# Receiver_Schematic.net
KiCad netlist of a schematic drawn in Altium Designer
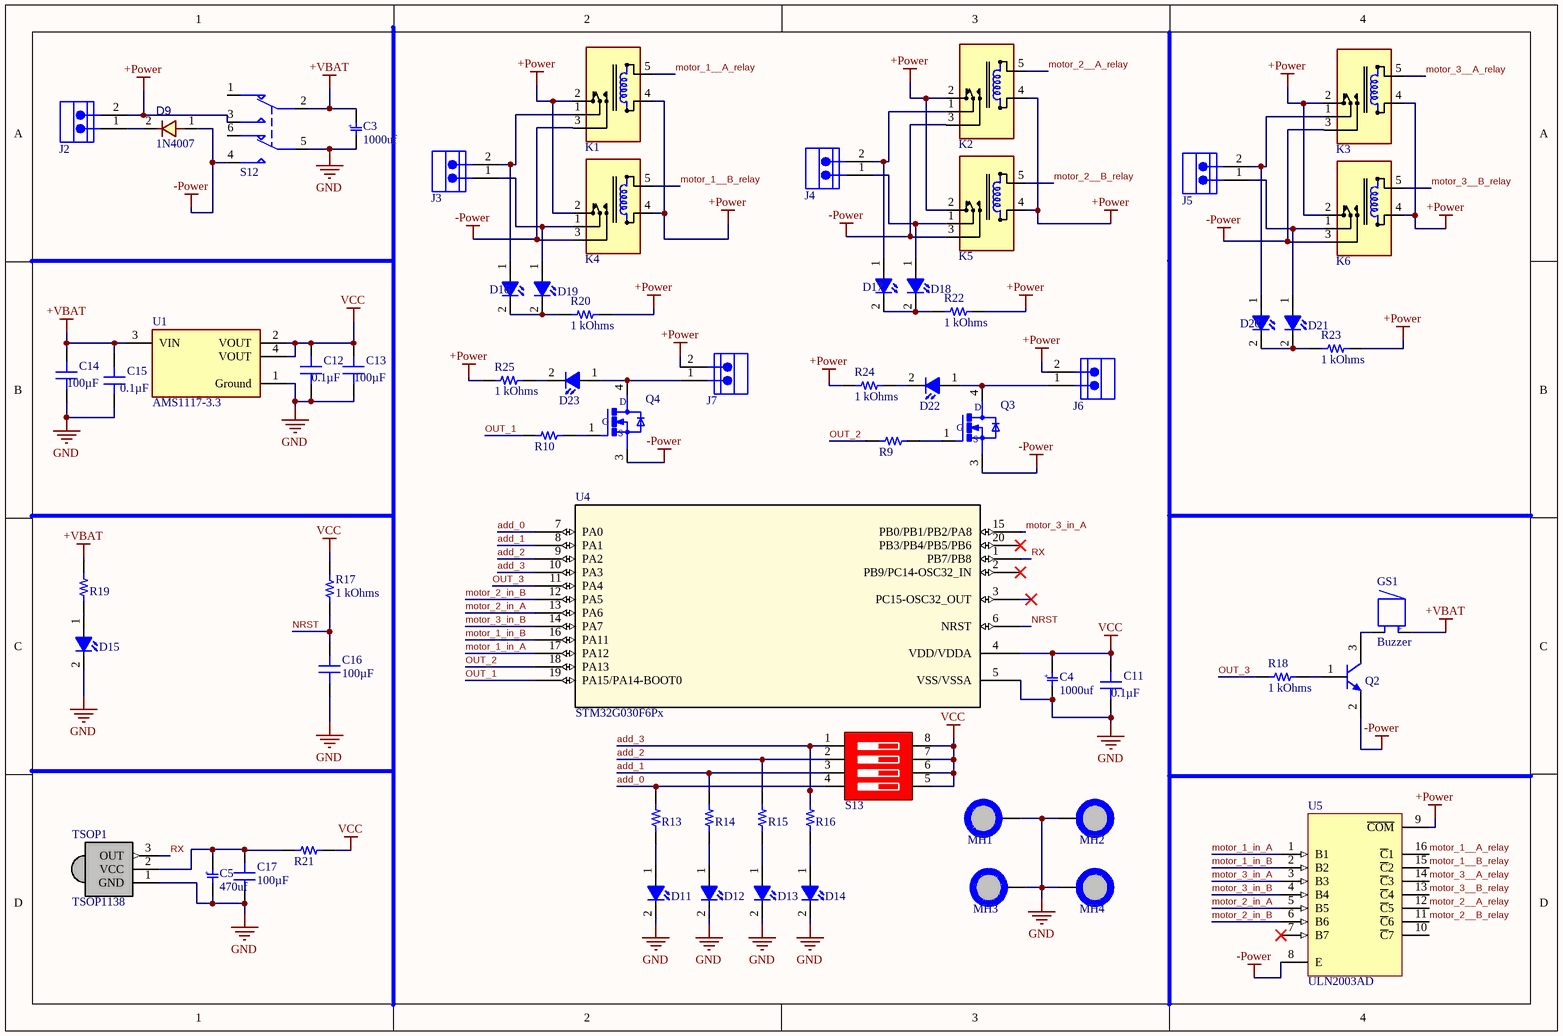
[diagram p0: Receiver_Schematic.SchDoc]

(export (version "E")
  (design (tool "Eeschema 10.0.6"))
  (components
    (comp (ref "C3")
      (value "1000uf")
      (footprint "Cap_3_(3.5mm)")
      (description "Capacitor Electrical THD")
      (libsource (lib "Schlib1") (part "Capacitor Electrical THD"))
    )
    (comp (ref "C4")
      (value "1000uf")
      (footprint "Cap_3_(3.5mm)")
      (description "Capacitor Electrical THD")
      (libsource (lib "Schlib1") (part "Capacitor Electrical THD"))
    )
    (comp (ref "C5")
      (value "470uf")
      (footprint "Cap_3_(3.5mm)")
      (description "Capacitor Electrical THD")
      (libsource (lib "Schlib1") (part "Capacitor Electrical THD"))
    )
    (comp (ref "C11")
      (value "0.1µF")
      (footprint "CAP 0805_2012")
      (description "CAP CER 0805 10% X8R 50V 100NF")
      (fields (field (name "PART NUMBER") "AC0805KKX8R9BB104") (field (name "MANUFACTURER") "Yageo"))
      (libsource (lib "Database_Libs1") (part "Capacitor"))
    )
    (comp (ref "C12")
      (value "0.1µF")
      (footprint "CAP 0805_2012")
      (description "CAP CER 0805 10% X8R 50V 100NF")
      (fields (field (name "PART NUMBER") "AC0805KKX8R9BB104") (field (name "MANUFACTURER") "Yageo"))
      (libsource (lib "Database_Libs1") (part "Capacitor"))
    )
    (comp (ref "C13")
      (value "100µF")
      (footprint "CAP 0805_2012")
      (description "CAP CER 100UF 6.3V X5R 0805")
      (fields
        (field (name "PART NUMBER") "GRM21BR60J107ME15L")
        (field (name "MANUFACTURER") "Murata Electronics")
      )
      (libsource (lib "Database_Libs1") (part "Capacitor"))
    )
    (comp (ref "C14")
      (value "100µF")
      (footprint "CAP 0805_2012")
      (description "CAP CER 100UF 6.3V X5R 0805")
      (fields
        (field (name "PART NUMBER") "GRM21BR60J107ME15L")
        (field (name "MANUFACTURER") "Murata Electronics")
      )
      (libsource (lib "Database_Libs1") (part "Capacitor"))
    )
    (comp (ref "C15")
      (value "0.1µF")
      (footprint "CAP 0805_2012")
      (description "CAP CER 0805 10% X8R 50V 100NF")
      (fields (field (name "PART NUMBER") "AC0805KKX8R9BB104") (field (name "MANUFACTURER") "Yageo"))
      (libsource (lib "Database_Libs1") (part "Capacitor"))
    )
    (comp (ref "C16")
      (value "100µF")
      (footprint "CAP 0805_2012")
      (description "CAP CER 100UF 6.3V X5R 0805")
      (fields
        (field (name "PART NUMBER") "GRM21BR60J107ME15L")
        (field (name "MANUFACTURER") "Murata Electronics")
      )
      (libsource (lib "Database_Libs1") (part "Capacitor"))
    )
    (comp (ref "C17")
      (value "100µF")
      (footprint "CAP 0805_2012")
      (description "CAP CER 100UF 6.3V X5R 0805")
      (fields
        (field (name "PART NUMBER") "GRM21BR60J107ME15L")
        (field (name "MANUFACTURER") "Murata Electronics")
      )
      (libsource (lib "Database_Libs1") (part "Capacitor"))
    )
    (comp (ref "D9")
      (value "1N4007")
      (footprint "D_SMA")
      (description "DIODE, GENERAL PURPOSE, 1000V/1A")
      (fields (field (name "Comment") "1N4007 SMD M7"))
      (libsource (lib "Schlib1") (part "1N4007 SMD M7"))
    )
    (comp (ref "D11")
      (value "LED THD 3mm")
      (footprint "LED THD 3mm (White)")
      (libsource (lib "Schlib1") (part "LED THD 3mm"))
    )
    (comp (ref "D12")
      (value "LED THD 3mm")
      (footprint "LED THD 3mm (White)")
      (libsource (lib "Schlib1") (part "LED THD 3mm"))
    )
    (comp (ref "D13")
      (value "LED THD 3mm")
      (footprint "LED THD 3mm (White)")
      (libsource (lib "Schlib1") (part "LED THD 3mm"))
    )
    (comp (ref "D14")
      (value "LED THD 3mm")
      (footprint "LED THD 3mm (White)")
      (libsource (lib "Schlib1") (part "LED THD 3mm"))
    )
    (comp (ref "D15")
      (value "LED THD 3mm")
      (footprint "LED THD 3mm (White)")
      (libsource (lib "Schlib1") (part "LED THD 3mm"))
    )
    (comp (ref "D16")
      (value "LED THD 3mm")
      (footprint "LED THD 3mm (White)")
      (libsource (lib "Schlib1") (part "LED THD 3mm"))
    )
    (comp (ref "D17")
      (value "LED THD 3mm")
      (footprint "LED THD 3mm (White)")
      (libsource (lib "Schlib1") (part "LED THD 3mm"))
    )
    (comp (ref "D18")
      (value "LED THD 3mm")
      (footprint "LED THD 3mm (White)")
      (libsource (lib "Schlib1") (part "LED THD 3mm"))
    )
    (comp (ref "D19")
      (value "LED THD 3mm")
      (footprint "LED THD 3mm (White)")
      (libsource (lib "Schlib1") (part "LED THD 3mm"))
    )
    (comp (ref "D20")
      (value "LED THD 3mm")
      (footprint "LED THD 3mm (White)")
      (libsource (lib "Schlib1") (part "LED THD 3mm"))
    )
    (comp (ref "D21")
      (value "LED THD 3mm")
      (footprint "LED THD 3mm (White)")
      (libsource (lib "Schlib1") (part "LED THD 3mm"))
    )
    (comp (ref "D22")
      (value "LED THD 3mm")
      (footprint "LED THD 3mm (White)")
      (libsource (lib "Schlib1") (part "LED THD 3mm"))
    )
    (comp (ref "D23")
      (value "LED THD 3mm")
      (footprint "LED THD 3mm (White)")
      (libsource (lib "Schlib1") (part "LED THD 3mm"))
    )
    (comp (ref "GS1")
      (value "Buzzer")
      (footprint "BZ_SJ")
      (description "Magnetic Transducer Buzzer")
      (fields (field (name "DESIGNER") "Eng. Saeid Jorablo") (field (name "PUBLISHER") "SJ Unlimited"))
      (libsource (lib "Schlib1") (part "Buzzer"))
    )
    (comp (ref "J2")
      (value "Socket Blue 2")
      (footprint "Socket Blue 2")
      (libsource (lib "Schlib1") (part "Socket Blue 2"))
    )
    (comp (ref "J3")
      (value "Socket Blue 2")
      (footprint "Socket Blue 2")
      (libsource (lib "Schlib1") (part "Socket Blue 2"))
    )
    (comp (ref "J4")
      (value "Socket Blue 2")
      (footprint "Socket Blue 2")
      (libsource (lib "Schlib1") (part "Socket Blue 2"))
    )
    (comp (ref "J5")
      (value "Socket Blue 2")
      (footprint "Socket Blue 2")
      (libsource (lib "Schlib1") (part "Socket Blue 2"))
    )
    (comp (ref "J6")
      (value "Socket Blue 2")
      (footprint "Socket Blue 2")
      (libsource (lib "Schlib1") (part "Socket Blue 2"))
    )
    (comp (ref "J7")
      (value "Socket Blue 2")
      (footprint "Socket Blue 2")
      (libsource (lib "Schlib1") (part "Socket Blue 2"))
    )
    (comp (ref "K1")
      (value "RELAY SPST 5 Pin Millon")
      (footprint "REL_SPDT_5_2216")
      (description "Relay")
      (libsource (lib "Schlib1") (part "RELAY SPST 5 Pin Millon"))
    )
    (comp (ref "K2")
      (value "RELAY SPST 5 Pin Millon")
      (footprint "REL_SPDT_5_2216")
      (description "Relay")
      (libsource (lib "Schlib1") (part "RELAY SPST 5 Pin Millon"))
    )
    (comp (ref "K3")
      (value "RELAY SPST 5 Pin Millon")
      (footprint "REL_SPDT_5_2216")
      (description "Relay")
      (libsource (lib "Schlib1") (part "RELAY SPST 5 Pin Millon"))
    )
    (comp (ref "K4")
      (value "RELAY SPST 5 Pin Millon")
      (footprint "REL_SPDT_5_2216")
      (description "Relay")
      (libsource (lib "Schlib1") (part "RELAY SPST 5 Pin Millon"))
    )
    (comp (ref "K5")
      (value "RELAY SPST 5 Pin Millon")
      (footprint "REL_SPDT_5_2216")
      (description "Relay")
      (libsource (lib "Schlib1") (part "RELAY SPST 5 Pin Millon"))
    )
    (comp (ref "K6")
      (value "RELAY SPST 5 Pin Millon")
      (footprint "REL_SPDT_5_2216")
      (description "Relay")
      (libsource (lib "Schlib1") (part "RELAY SPST 5 Pin Millon"))
    )
    (comp (ref "MH1")
      (value "MH_7.4mmC_3.2mmD")
      (footprint "MH_7.4mmC_3.2mmD")
      (description "MH_7.4MM Diameter,3.2mm Drill")
      (libsource (lib "Schlib1") (part "MH_7.4mmC_3.2mmD"))
    )
    (comp (ref "MH2")
      (value "MH_7.4mmC_3.2mmD")
      (footprint "MH_7.4mmC_3.2mmD")
      (description "MH_7.4MM Diameter,3.2mm Drill")
      (libsource (lib "Schlib1") (part "MH_7.4mmC_3.2mmD"))
    )
    (comp (ref "MH3")
      (value "MH_7.4mmC_3.2mmD")
      (footprint "MH_7.4mmC_3.2mmD")
      (description "MH_7.4MM Diameter,3.2mm Drill")
      (libsource (lib "Schlib1") (part "MH_7.4mmC_3.2mmD"))
    )
    (comp (ref "MH4")
      (value "MH_7.4mmC_3.2mmD")
      (footprint "MH_7.4mmC_3.2mmD")
      (description "MH_7.4MM Diameter,3.2mm Drill")
      (libsource (lib "Schlib1") (part "MH_7.4mmC_3.2mmD"))
    )
    (comp (ref "Q2")
      (value "MMBT2222A-7-F")
      (footprint "DIODES SOT-23-3")
      (description "TRANS NPN 40V 0.6A SMD SOT23-3")
      (fields (field (name "MANUFACTURER") "Diodes Incorporated"))
      (libsource (lib "Database_Libs1") (part "DIODES INC NPN SOT-23-3"))
    )
    (comp (ref "Q3")
      (value "PHD45N03LTA")
      (footprint "PcbLib1:TO228P1000X238-3N")
      (description "Bipolar Transistors - BJT")
      (fields (field (name "MF") "NXP USA"))
      (libsource (lib "Schlib1") (part "PHD45N03LTA"))
    )
    (comp (ref "Q4")
      (value "PHD45N03LTA")
      (footprint "PcbLib1:TO228P1000X238-3N")
      (description "Bipolar Transistors - BJT")
      (fields (field (name "MF") "NXP USA"))
      (libsource (lib "Schlib1") (part "PHD45N03LTA"))
    )
    (comp (ref "R9")
      (value "100 Ohms")
      (footprint "RES 0805_2012")
      (description "RES SMD 100 OHM 1% 0.4W 0805")
      (fields (field (name "PART NUMBER") "RCS0805100RFKEA") (field (name "MANUFACTURER") "Vishay Dale"))
      (libsource (lib "Database_Libs1") (part "Resistor"))
    )
    (comp (ref "R10")
      (value "100 Ohms")
      (footprint "RES 0805_2012")
      (description "RES SMD 100 OHM 1% 0.4W 0805")
      (fields (field (name "PART NUMBER") "RCS0805100RFKEA") (field (name "MANUFACTURER") "Vishay Dale"))
      (libsource (lib "Database_Libs1") (part "Resistor"))
    )
    (comp (ref "R13")
      (value "50 mOhms")
      (footprint "RES 0805_2012")
      (description "RES 0.05 OHM 1% 1/4W 0805")
      (fields (field (name "PART NUMBER") "CRM0805-FW-R050ELF") (field (name "MANUFACTURER") "Bourns Inc."))
      (libsource (lib "Database_Libs1") (part "Resistor"))
    )
    (comp (ref "R14")
      (value "50 mOhms")
      (footprint "RES 0805_2012")
      (description "RES 0.05 OHM 1% 1/4W 0805")
      (fields (field (name "PART NUMBER") "CRM0805-FW-R050ELF") (field (name "MANUFACTURER") "Bourns Inc."))
      (libsource (lib "Database_Libs1") (part "Resistor"))
    )
    (comp (ref "R15")
      (value "50 mOhms")
      (footprint "RES 0805_2012")
      (description "RES 0.05 OHM 1% 1/4W 0805")
      (fields (field (name "PART NUMBER") "CRM0805-FW-R050ELF") (field (name "MANUFACTURER") "Bourns Inc."))
      (libsource (lib "Database_Libs1") (part "Resistor"))
    )
    (comp (ref "R16")
      (value "50 mOhms")
      (footprint "RES 0805_2012")
      (description "RES 0.05 OHM 1% 1/4W 0805")
      (fields (field (name "PART NUMBER") "CRM0805-FW-R050ELF") (field (name "MANUFACTURER") "Bourns Inc."))
      (libsource (lib "Database_Libs1") (part "Resistor"))
    )
    (comp (ref "R17")
      (value "1 kOhms")
      (footprint "RES 0805_2012")
      (description "RES 1K OHM 1% 1/4W 0805")
      (fields
        (field (name "PART NUMBER") "RNCP0805FTD1K00")
        (field (name "MANUFACTURER") "Stackpole Electronics Inc")
      )
      (libsource (lib "Database_Libs1") (part "Resistor"))
    )
    (comp (ref "R18")
      (value "1 kOhms")
      (footprint "RES 0805_2012")
      (description "RES 1K OHM 1% 1/4W 0805")
      (fields
        (field (name "PART NUMBER") "RNCP0805FTD1K00")
        (field (name "MANUFACTURER") "Stackpole Electronics Inc")
      )
      (libsource (lib "Database_Libs1") (part "Resistor"))
    )
    (comp (ref "R19")
      (value "150 Ohms")
      (footprint "RES 0805_2012")
      (description "CRGP 0805 150R 1%")
      (fields
        (field (name "PART NUMBER") "CRGP0805F150R")
        (field (name "MANUFACTURER") "TE Connectivity Passive Product")
      )
      (libsource (lib "Database_Libs1") (part "Resistor"))
    )
    (comp (ref "R20")
      (value "1 kOhms")
      (footprint "RES 0805_2012")
      (description "RES 1K OHM 1% 1/4W 0805")
      (fields
        (field (name "PART NUMBER") "RNCP0805FTD1K00")
        (field (name "MANUFACTURER") "Stackpole Electronics Inc")
      )
      (libsource (lib "Database_Libs1") (part "Resistor"))
    )
    (comp (ref "R21")
      (value "100 Ohms")
      (footprint "RES 0805_2012")
      (description "CRGP 0805 100R 1%")
      (fields
        (field (name "PART NUMBER") "CRGP0805F100R")
        (field (name "MANUFACTURER") "TE Connectivity Passive Product")
      )
      (libsource (lib "Database_Libs1") (part "Resistor"))
    )
    (comp (ref "R22")
      (value "1 kOhms")
      (footprint "RES 0805_2012")
      (description "RES 1K OHM 1% 1/4W 0805")
      (fields
        (field (name "PART NUMBER") "RNCP0805FTD1K00")
        (field (name "MANUFACTURER") "Stackpole Electronics Inc")
      )
      (libsource (lib "Database_Libs1") (part "Resistor"))
    )
    (comp (ref "R23")
      (value "1 kOhms")
      (footprint "RES 0805_2012")
      (description "RES 1K OHM 1% 1/4W 0805")
      (fields
        (field (name "PART NUMBER") "RNCP0805FTD1K00")
        (field (name "MANUFACTURER") "Stackpole Electronics Inc")
      )
      (libsource (lib "Database_Libs1") (part "Resistor"))
    )
    (comp (ref "R24")
      (value "1 kOhms")
      (footprint "RES 0805_2012")
      (description "RES 1K OHM 1% 1/4W 0805")
      (fields
        (field (name "PART NUMBER") "RNCP0805FTD1K00")
        (field (name "MANUFACTURER") "Stackpole Electronics Inc")
      )
      (libsource (lib "Database_Libs1") (part "Resistor"))
    )
    (comp (ref "R25")
      (value "1 kOhms")
      (footprint "RES 0805_2012")
      (description "RES 1K OHM 1% 1/4W 0805")
      (fields
        (field (name "PART NUMBER") "RNCP0805FTD1K00")
        (field (name "MANUFACTURER") "Stackpole Electronics Inc")
      )
      (libsource (lib "Database_Libs1") (part "Resistor"))
    )
    (comp (ref "S12")
      (value "Double Switch")
      (footprint "SWPUST_DPDT_S2")
      (description "DPDT Switch")
      (libsource (lib "Schlib1") (part "SW DPDT"))
    )
    (comp (ref "S13")
      (value "DIP Switch 4")
      (footprint "dip switch 4  Blue THD")
      (description "4 BIT DIP Switch")
      (libsource (lib "Schlib1") (part "DIP Switch 4"))
    )
    (comp (ref "TSOP1")
      (value "TSOP1138")
      (footprint "TSOP11XX & 13XX")
      (description "IR Receiver Modules for Remote Control Systems")
      (libsource (lib "Schlib1") (part "TSOP1138"))
    )
    (comp (ref "U1")
      (value "AMS1117-3.3")
      (footprint "SOT223-4N")
      (description "LDO Voltage Regulators 1A, 3.3V")
      (fields
        (field (name "OCTOPART") "https://octopart.com/ams1117-3.3-advanced+monolithic+systems-25899300")
        (field (name "MANUFACTURER") "Advanced Monolithic Systems")
      )
      (libsource (lib "Schlib1") (part "CMP-209535-000001-1"))
    )
    (comp (ref "U4")
      (value "STM32G030F6Px")
      (footprint "TSSOP20")
      (fields
        (field (name "MANUFACTURER_PART_NUMBER") "stm32g0_tssop20_t1")
        (field (name "COPYRIGHT") "Copyright (C) 2018 Accelerated Designs. All rights reserved")
      )
      (libsource (lib "ST Microelectronics STM32 G0") (part "STM32G030F6Px"))
    )
    (comp (ref "U5")
      (value "ULN2003AD")
      (footprint "SOIC16")
      (description "Darlington Transistor Array")
      (fields (field (name "PUBLISHER") "Altium Limited"))
      (libsource (lib "Schlib1") (part "ULN2003AD"))
    )
  )
  (nets
    (net (code "1") (name "+Power") (class "Default")
      (node (ref "J2") (pin "2") (pinfunction "2_2") (pintype "passive"))
      (node (ref "J6") (pin "2") (pinfunction "2_2") (pintype "passive"))
      (node (ref "J7") (pin "2") (pinfunction "2_2") (pintype "passive"))
      (node (ref "K1") (pin "2") (pinfunction "NC_2") (pintype "passive"))
      (node (ref "K1") (pin "4") (pinfunction "T1_4") (pintype "passive"))
      (node (ref "K2") (pin "2") (pinfunction "NC_2") (pintype "passive"))
      (node (ref "K2") (pin "4") (pinfunction "T1_4") (pintype "passive"))
      (node (ref "K3") (pin "2") (pinfunction "NC_2") (pintype "passive"))
      (node (ref "K3") (pin "4") (pinfunction "T1_4") (pintype "passive"))
      (node (ref "K4") (pin "2") (pinfunction "NC_2") (pintype "passive"))
      (node (ref "K4") (pin "4") (pinfunction "T1_4") (pintype "passive"))
      (node (ref "K5") (pin "2") (pinfunction "NC_2") (pintype "passive"))
      (node (ref "K5") (pin "4") (pinfunction "T1_4") (pintype "passive"))
      (node (ref "K6") (pin "2") (pinfunction "NC_2") (pintype "passive"))
      (node (ref "K6") (pin "4") (pinfunction "T1_4") (pintype "passive"))
      (node (ref "R20") (pin "2") (pinfunction "2_2") (pintype "passive"))
      (node (ref "R22") (pin "2") (pinfunction "2_2") (pintype "passive"))
      (node (ref "R23") (pin "2") (pinfunction "2_2") (pintype "passive"))
      (node (ref "R24") (pin "1") (pinfunction "1_1") (pintype "passive"))
      (node (ref "R25") (pin "1") (pinfunction "1_1") (pintype "passive"))
      (node (ref "S12") (pin "3") (pinfunction "3_3") (pintype "passive"))
      (node (ref "U5") (pin "9") (pinfunction "~{COM}_9") (pintype "passive"))
    )
    (net (code "2") (name "+VBAT") (class "Default")
      (node (ref "C14") (pin "2") (pinfunction "2_2") (pintype "passive"))
      (node (ref "C15") (pin "2") (pinfunction "2_2") (pintype "passive"))
      (node (ref "C3") (pin "1") (pinfunction "1_1") (pintype "passive"))
      (node (ref "GS1") (pin "1") (pinfunction "+_1") (pintype "passive"))
      (node (ref "R19") (pin "2") (pinfunction "2_2") (pintype "passive"))
      (node (ref "S12") (pin "2") (pinfunction "2_2") (pintype "passive"))
      (node (ref "U1") (pin "3") (pinfunction "VIN_3") (pintype "power_in"))
    )
    (net (code "3") (name "-Power") (class "Default")
      (node (ref "D9") (pin "1") (pinfunction "1_1") (pintype "passive"))
      (node (ref "K1") (pin "3") (pinfunction "NO_3") (pintype "passive"))
      (node (ref "K2") (pin "3") (pinfunction "NO_3") (pintype "passive"))
      (node (ref "K3") (pin "3") (pinfunction "NO_3") (pintype "passive"))
      (node (ref "K4") (pin "3") (pinfunction "NO_3") (pintype "passive"))
      (node (ref "K5") (pin "3") (pinfunction "NO_3") (pintype "passive"))
      (node (ref "K6") (pin "3") (pinfunction "NO_3") (pintype "passive"))
      (node (ref "Q2") (pin "2") (pinfunction "E_2") (pintype "passive"))
      (node (ref "Q3") (pin "3") (pinfunction "S_3") (pintype "passive"))
      (node (ref "Q4") (pin "3") (pinfunction "S_3") (pintype "passive"))
      (node (ref "S12") (pin "4") (pinfunction "4_4") (pintype "passive"))
      (node (ref "U5") (pin "8") (pinfunction "E_8") (pintype "power_in"))
    )
    (net (code "4") (name "/NRST") (class "Default")
      (node (ref "C16") (pin "2") (pinfunction "2_2") (pintype "passive"))
      (node (ref "R17") (pin "2") (pinfunction "2_2") (pintype "passive"))
      (node (ref "U4") (pin "6") (pinfunction "NRST_6") (pintype "bidirectional"))
    )
    (net (code "5") (name "/OUT_1") (class "Default")
      (node (ref "R10") (pin "1") (pinfunction "1_1") (pintype "passive"))
      (node (ref "U4") (pin "19") (pinfunction "PA15/PA14-BOOT0_19") (pintype "bidirectional"))
    )
    (net (code "6") (name "/OUT_2") (class "Default")
      (node (ref "R9") (pin "1") (pinfunction "1_1") (pintype "passive"))
      (node (ref "U4") (pin "18") (pinfunction "PA13_18") (pintype "bidirectional"))
    )
    (net (code "7") (name "/OUT_3") (class "Default")
      (node (ref "R18") (pin "1") (pinfunction "1_1") (pintype "passive"))
      (node (ref "U4") (pin "11") (pinfunction "PA4_11") (pintype "bidirectional"))
    )
    (net (code "8") (name "/RX") (class "Default")
      (node (ref "TSOP1") (pin "3") (pinfunction "OUT_3") (pintype "output"))
      (node (ref "U4") (pin "1") (pinfunction "PB7/PB8_1") (pintype "bidirectional"))
    )
    (net (code "9") (name "/add_0") (class "Default")
      (node (ref "R13") (pin "2") (pinfunction "2_2") (pintype "passive"))
      (node (ref "S13") (pin "4") (pinfunction "4_4") (pintype "passive"))
      (node (ref "U4") (pin "7") (pinfunction "PA0_7") (pintype "bidirectional"))
    )
    (net (code "10") (name "/add_1") (class "Default")
      (node (ref "R14") (pin "2") (pinfunction "2_2") (pintype "passive"))
      (node (ref "S13") (pin "3") (pinfunction "3_3") (pintype "passive"))
      (node (ref "U4") (pin "8") (pinfunction "PA1_8") (pintype "bidirectional"))
    )
    (net (code "11") (name "/add_2") (class "Default")
      (node (ref "R15") (pin "2") (pinfunction "2_2") (pintype "passive"))
      (node (ref "S13") (pin "2") (pinfunction "2_2") (pintype "passive"))
      (node (ref "U4") (pin "9") (pinfunction "PA2_9") (pintype "bidirectional"))
    )
    (net (code "12") (name "/add_3") (class "Default")
      (node (ref "R16") (pin "2") (pinfunction "2_2") (pintype "passive"))
      (node (ref "S13") (pin "1") (pinfunction "1_1") (pintype "passive"))
      (node (ref "U4") (pin "10") (pinfunction "PA3_10") (pintype "bidirectional"))
    )
    (net (code "13") (name "/motor_1__A_relay") (class "Default")
      (node (ref "K1") (pin "5") (pinfunction "T2_5") (pintype "passive"))
      (node (ref "U5") (pin "16") (pinfunction "~{C}1_16") (pintype "open_collector"))
    )
    (net (code "14") (name "/motor_1__B_relay") (class "Default")
      (node (ref "K4") (pin "5") (pinfunction "T2_5") (pintype "passive"))
      (node (ref "U5") (pin "15") (pinfunction "~{C}2_15") (pintype "open_collector"))
    )
    (net (code "15") (name "/motor_1_in_A") (class "Default")
      (node (ref "U4") (pin "17") (pinfunction "PA12_17") (pintype "bidirectional"))
      (node (ref "U5") (pin "1") (pinfunction "B1_1") (pintype "input"))
    )
    (net (code "16") (name "/motor_1_in_B") (class "Default")
      (node (ref "U4") (pin "16") (pinfunction "PA11_16") (pintype "bidirectional"))
      (node (ref "U5") (pin "2") (pinfunction "B2_2") (pintype "input"))
    )
    (net (code "17") (name "/motor_2__A_relay") (class "Default")
      (node (ref "K2") (pin "5") (pinfunction "T2_5") (pintype "passive"))
      (node (ref "U5") (pin "12") (pinfunction "~{C}5_12") (pintype "open_collector"))
    )
    (net (code "18") (name "/motor_2__B_relay") (class "Default")
      (node (ref "K5") (pin "5") (pinfunction "T2_5") (pintype "passive"))
      (node (ref "U5") (pin "11") (pinfunction "~{C}6_11") (pintype "open_collector"))
    )
    (net (code "19") (name "/motor_2_in_A") (class "Default")
      (node (ref "U4") (pin "13") (pinfunction "PA6_13") (pintype "bidirectional"))
      (node (ref "U5") (pin "5") (pinfunction "B5_5") (pintype "input"))
    )
    (net (code "20") (name "/motor_2_in_B") (class "Default")
      (node (ref "U4") (pin "12") (pinfunction "PA5_12") (pintype "bidirectional"))
      (node (ref "U5") (pin "6") (pinfunction "B6_6") (pintype "input"))
    )
    (net (code "21") (name "/motor_3__A_relay") (class "Default")
      (node (ref "K3") (pin "5") (pinfunction "T2_5") (pintype "passive"))
      (node (ref "U5") (pin "14") (pinfunction "~{C}3_14") (pintype "open_collector"))
    )
    (net (code "22") (name "/motor_3__B_relay") (class "Default")
      (node (ref "K6") (pin "5") (pinfunction "T2_5") (pintype "passive"))
      (node (ref "U5") (pin "13") (pinfunction "~{C}4_13") (pintype "open_collector"))
    )
    (net (code "23") (name "/motor_3_in_A") (class "Default")
      (node (ref "U4") (pin "15") (pinfunction "PB0/PB1/PB2/PA8_15") (pintype "bidirectional"))
      (node (ref "U5") (pin "3") (pinfunction "B3_3") (pintype "input"))
    )
    (net (code "24") (name "/motor_3_in_B") (class "Default")
      (node (ref "U4") (pin "14") (pinfunction "PA7_14") (pintype "bidirectional"))
      (node (ref "U5") (pin "4") (pinfunction "B4_4") (pintype "input"))
    )
    (net (code "25") (name "GND") (class "Default")
      (node (ref "C11") (pin "1") (pinfunction "1_1") (pintype "passive"))
      (node (ref "C12") (pin "1") (pinfunction "1_1") (pintype "passive"))
      (node (ref "C13") (pin "1") (pinfunction "1_1") (pintype "passive"))
      (node (ref "C14") (pin "1") (pinfunction "1_1") (pintype "passive"))
      (node (ref "C15") (pin "1") (pinfunction "1_1") (pintype "passive"))
      (node (ref "C16") (pin "1") (pinfunction "1_1") (pintype "passive"))
      (node (ref "C17") (pin "1") (pinfunction "1_1") (pintype "passive"))
      (node (ref "C3") (pin "2") (pinfunction "2_2") (pintype "passive"))
      (node (ref "C4") (pin "2") (pinfunction "2_2") (pintype "passive"))
      (node (ref "C5") (pin "2") (pinfunction "2_2") (pintype "passive"))
      (node (ref "D11") (pin "2") (pinfunction "CATHODE_2") (pintype "passive"))
      (node (ref "D12") (pin "2") (pinfunction "CATHODE_2") (pintype "passive"))
      (node (ref "D13") (pin "2") (pinfunction "CATHODE_2") (pintype "passive"))
      (node (ref "D14") (pin "2") (pinfunction "CATHODE_2") (pintype "passive"))
      (node (ref "D15") (pin "2") (pinfunction "CATHODE_2") (pintype "passive"))
      (node (ref "MH1") (pin "0") (pinfunction "0_0") (pintype "passive"))
      (node (ref "MH2") (pin "0") (pinfunction "0_0") (pintype "passive"))
      (node (ref "MH3") (pin "0") (pinfunction "0_0") (pintype "passive"))
      (node (ref "MH4") (pin "0") (pinfunction "0_0") (pintype "passive"))
      (node (ref "S12") (pin "5") (pinfunction "5_5") (pintype "passive"))
      (node (ref "TSOP1") (pin "1") (pinfunction "GND_1") (pintype "power_in"))
      (node (ref "U1") (pin "1") (pinfunction "Ground_1") (pintype "power_in"))
      (node (ref "U4") (pin "5") (pinfunction "VSS/VSSA_5") (pintype "power_in"))
    )
    (net (code "26") (name "Net-(D9-Pad2)") (class "Default")
      (node (ref "D9") (pin "2") (pinfunction "2_2") (pintype "passive"))
      (node (ref "J2") (pin "1") (pinfunction "1_1") (pintype "passive"))
    )
    (net (code "27") (name "Net-(D11-ANODE)") (class "Default")
      (node (ref "D11") (pin "1") (pinfunction "ANODE_1") (pintype "passive"))
      (node (ref "R13") (pin "1") (pinfunction "1_1") (pintype "passive"))
    )
    (net (code "28") (name "Net-(D12-ANODE)") (class "Default")
      (node (ref "D12") (pin "1") (pinfunction "ANODE_1") (pintype "passive"))
      (node (ref "R14") (pin "1") (pinfunction "1_1") (pintype "passive"))
    )
    (net (code "29") (name "Net-(D13-ANODE)") (class "Default")
      (node (ref "D13") (pin "1") (pinfunction "ANODE_1") (pintype "passive"))
      (node (ref "R15") (pin "1") (pinfunction "1_1") (pintype "passive"))
    )
    (net (code "30") (name "Net-(D14-ANODE)") (class "Default")
      (node (ref "D14") (pin "1") (pinfunction "ANODE_1") (pintype "passive"))
      (node (ref "R16") (pin "1") (pinfunction "1_1") (pintype "passive"))
    )
    (net (code "31") (name "Net-(D15-ANODE)") (class "Default")
      (node (ref "D15") (pin "1") (pinfunction "ANODE_1") (pintype "passive"))
      (node (ref "R19") (pin "1") (pinfunction "1_1") (pintype "passive"))
    )
    (net (code "32") (name "Net-(D16-ANODE)") (class "Default")
      (node (ref "D16") (pin "1") (pinfunction "ANODE_1") (pintype "passive"))
      (node (ref "J3") (pin "2") (pinfunction "2_2") (pintype "passive"))
      (node (ref "K1") (pin "1") (pinfunction "COM_1") (pintype "passive"))
    )
    (net (code "33") (name "Net-(D16-CATHODE)") (class "Default")
      (node (ref "D16") (pin "2") (pinfunction "CATHODE_2") (pintype "passive"))
      (node (ref "D19") (pin "2") (pinfunction "CATHODE_2") (pintype "passive"))
      (node (ref "R20") (pin "1") (pinfunction "1_1") (pintype "passive"))
    )
    (net (code "34") (name "Net-(D17-ANODE)") (class "Default")
      (node (ref "D17") (pin "1") (pinfunction "ANODE_1") (pintype "passive"))
      (node (ref "J4") (pin "2") (pinfunction "2_2") (pintype "passive"))
      (node (ref "K2") (pin "1") (pinfunction "COM_1") (pintype "passive"))
    )
    (net (code "35") (name "Net-(D17-CATHODE)") (class "Default")
      (node (ref "D17") (pin "2") (pinfunction "CATHODE_2") (pintype "passive"))
      (node (ref "D18") (pin "2") (pinfunction "CATHODE_2") (pintype "passive"))
      (node (ref "R22") (pin "1") (pinfunction "1_1") (pintype "passive"))
    )
    (net (code "36") (name "Net-(D18-ANODE)") (class "Default")
      (node (ref "D18") (pin "1") (pinfunction "ANODE_1") (pintype "passive"))
      (node (ref "J4") (pin "1") (pinfunction "1_1") (pintype "passive"))
      (node (ref "K5") (pin "1") (pinfunction "COM_1") (pintype "passive"))
    )
    (net (code "37") (name "Net-(D19-ANODE)") (class "Default")
      (node (ref "D19") (pin "1") (pinfunction "ANODE_1") (pintype "passive"))
      (node (ref "J3") (pin "1") (pinfunction "1_1") (pintype "passive"))
      (node (ref "K4") (pin "1") (pinfunction "COM_1") (pintype "passive"))
    )
    (net (code "38") (name "Net-(D20-ANODE)") (class "Default")
      (node (ref "D20") (pin "1") (pinfunction "ANODE_1") (pintype "passive"))
      (node (ref "J5") (pin "2") (pinfunction "2_2") (pintype "passive"))
      (node (ref "K3") (pin "1") (pinfunction "COM_1") (pintype "passive"))
    )
    (net (code "39") (name "Net-(D20-CATHODE)") (class "Default")
      (node (ref "D20") (pin "2") (pinfunction "CATHODE_2") (pintype "passive"))
      (node (ref "D21") (pin "2") (pinfunction "CATHODE_2") (pintype "passive"))
      (node (ref "R23") (pin "1") (pinfunction "1_1") (pintype "passive"))
    )
    (net (code "40") (name "Net-(D21-ANODE)") (class "Default")
      (node (ref "D21") (pin "1") (pinfunction "ANODE_1") (pintype "passive"))
      (node (ref "J5") (pin "1") (pinfunction "1_1") (pintype "passive"))
      (node (ref "K6") (pin "1") (pinfunction "COM_1") (pintype "passive"))
    )
    (net (code "41") (name "Net-(D22-ANODE)") (class "Default")
      (node (ref "D22") (pin "1") (pinfunction "ANODE_1") (pintype "passive"))
      (node (ref "J6") (pin "1") (pinfunction "1_1") (pintype "passive"))
      (node (ref "Q3") (pin "4") (pinfunction "D_4") (pintype "passive"))
    )
    (net (code "42") (name "Net-(D22-CATHODE)") (class "Default")
      (node (ref "D22") (pin "2") (pinfunction "CATHODE_2") (pintype "passive"))
      (node (ref "R24") (pin "2") (pinfunction "2_2") (pintype "passive"))
    )
    (net (code "43") (name "Net-(D23-ANODE)") (class "Default")
      (node (ref "D23") (pin "1") (pinfunction "ANODE_1") (pintype "passive"))
      (node (ref "J7") (pin "1") (pinfunction "1_1") (pintype "passive"))
      (node (ref "Q4") (pin "4") (pinfunction "D_4") (pintype "passive"))
    )
    (net (code "44") (name "Net-(D23-CATHODE)") (class "Default")
      (node (ref "D23") (pin "2") (pinfunction "CATHODE_2") (pintype "passive"))
      (node (ref "R25") (pin "2") (pinfunction "2_2") (pintype "passive"))
    )
    (net (code "45") (name "Net-(GS1--)") (class "Default")
      (node (ref "GS1") (pin "2") (pinfunction "-_2") (pintype "passive"))
      (node (ref "Q2") (pin "3") (pinfunction "C_3") (pintype "passive"))
    )
    (net (code "46") (name "Net-(Q2-B)") (class "Default")
      (node (ref "Q2") (pin "1") (pinfunction "B_1") (pintype "passive"))
      (node (ref "R18") (pin "2") (pinfunction "2_2") (pintype "passive"))
    )
    (net (code "47") (name "Net-(Q3-G)") (class "Default")
      (node (ref "Q3") (pin "1") (pinfunction "G_1") (pintype "passive"))
      (node (ref "R9") (pin "2") (pinfunction "2_2") (pintype "passive"))
    )
    (net (code "48") (name "Net-(Q4-G)") (class "Default")
      (node (ref "Q4") (pin "1") (pinfunction "G_1") (pintype "passive"))
      (node (ref "R10") (pin "2") (pinfunction "2_2") (pintype "passive"))
    )
    (net (code "49") (name "Net-(TSOP1-VCC)") (class "Default")
      (node (ref "C17") (pin "2") (pinfunction "2_2") (pintype "passive"))
      (node (ref "C5") (pin "1") (pinfunction "1_1") (pintype "passive"))
      (node (ref "R21") (pin "1") (pinfunction "1_1") (pintype "passive"))
      (node (ref "TSOP1") (pin "2") (pinfunction "VCC_2") (pintype "power_in"))
    )
    (net (code "50") (name "VCC") (class "Default")
      (node (ref "C11") (pin "2") (pinfunction "2_2") (pintype "passive"))
      (node (ref "C12") (pin "2") (pinfunction "2_2") (pintype "passive"))
      (node (ref "C13") (pin "2") (pinfunction "2_2") (pintype "passive"))
      (node (ref "C4") (pin "1") (pinfunction "1_1") (pintype "passive"))
      (node (ref "R17") (pin "1") (pinfunction "1_1") (pintype "passive"))
      (node (ref "R21") (pin "2") (pinfunction "2_2") (pintype "passive"))
      (node (ref "S13") (pin "5") (pinfunction "5_5") (pintype "passive"))
      (node (ref "S13") (pin "6") (pinfunction "6_6") (pintype "passive"))
      (node (ref "S13") (pin "7") (pinfunction "7_7") (pintype "passive"))
      (node (ref "S13") (pin "8") (pinfunction "8_8") (pintype "passive"))
      (node (ref "U1") (pin "2") (pinfunction "VOUT_2") (pintype "passive"))
      (node (ref "U1") (pin "4") (pinfunction "VOUT_4") (pintype "passive"))
      (node (ref "U4") (pin "4") (pinfunction "VDD/VDDA_4") (pintype "power_in"))
    )
    (net (code "51") (name "unconnected-(S12-Pad1)") (class "Default")
      (node (ref "S12") (pin "1") (pinfunction "1_1") (pintype "passive"))
    )
    (net (code "52") (name "unconnected-(S12-Pad6)") (class "Default")
      (node (ref "S12") (pin "6") (pinfunction "6_6") (pintype "passive"))
    )
    (net (code "53") (name "unconnected-(U4-PB3{slash}PB4{slash}PB5{slash}PB6-Pad20)") (class "Default")
      (node (ref "U4") (pin "20") (pinfunction "PB3/PB4/PB5/PB6_20") (pintype "bidirectional+no_connect"))
    )
    (net (code "54") (name "unconnected-(U4-PB9{slash}PC14-OSC32_IN-Pad2)") (class "Default")
      (node (ref "U4") (pin "2") (pinfunction "PB9/PC14-OSC32_IN_2") (pintype "bidirectional+no_connect"))
    )
    (net (code "55") (name "unconnected-(U4-PC15-OSC32_OUT-Pad3)") (class "Default")
      (node (ref "U4") (pin "3") (pinfunction "PC15-OSC32_OUT_3") (pintype "bidirectional+no_connect"))
    )
    (net (code "56") (name "unconnected-(U5-B7-Pad7)") (class "Default")
      (node (ref "U5") (pin "7") (pinfunction "B7_7") (pintype "input+no_connect"))
    )
    (net (code "57") (name "unconnected-(U5-~{C}7-Pad10)") (class "Default")
      (node (ref "U5") (pin "10") (pinfunction "~{C}7_10") (pintype "open_collector"))
    )
  )
)
